# SCH_NFC_Business_Card_2024-01-20.net
KiCad netlist of a schematic drawn in EasyEDA
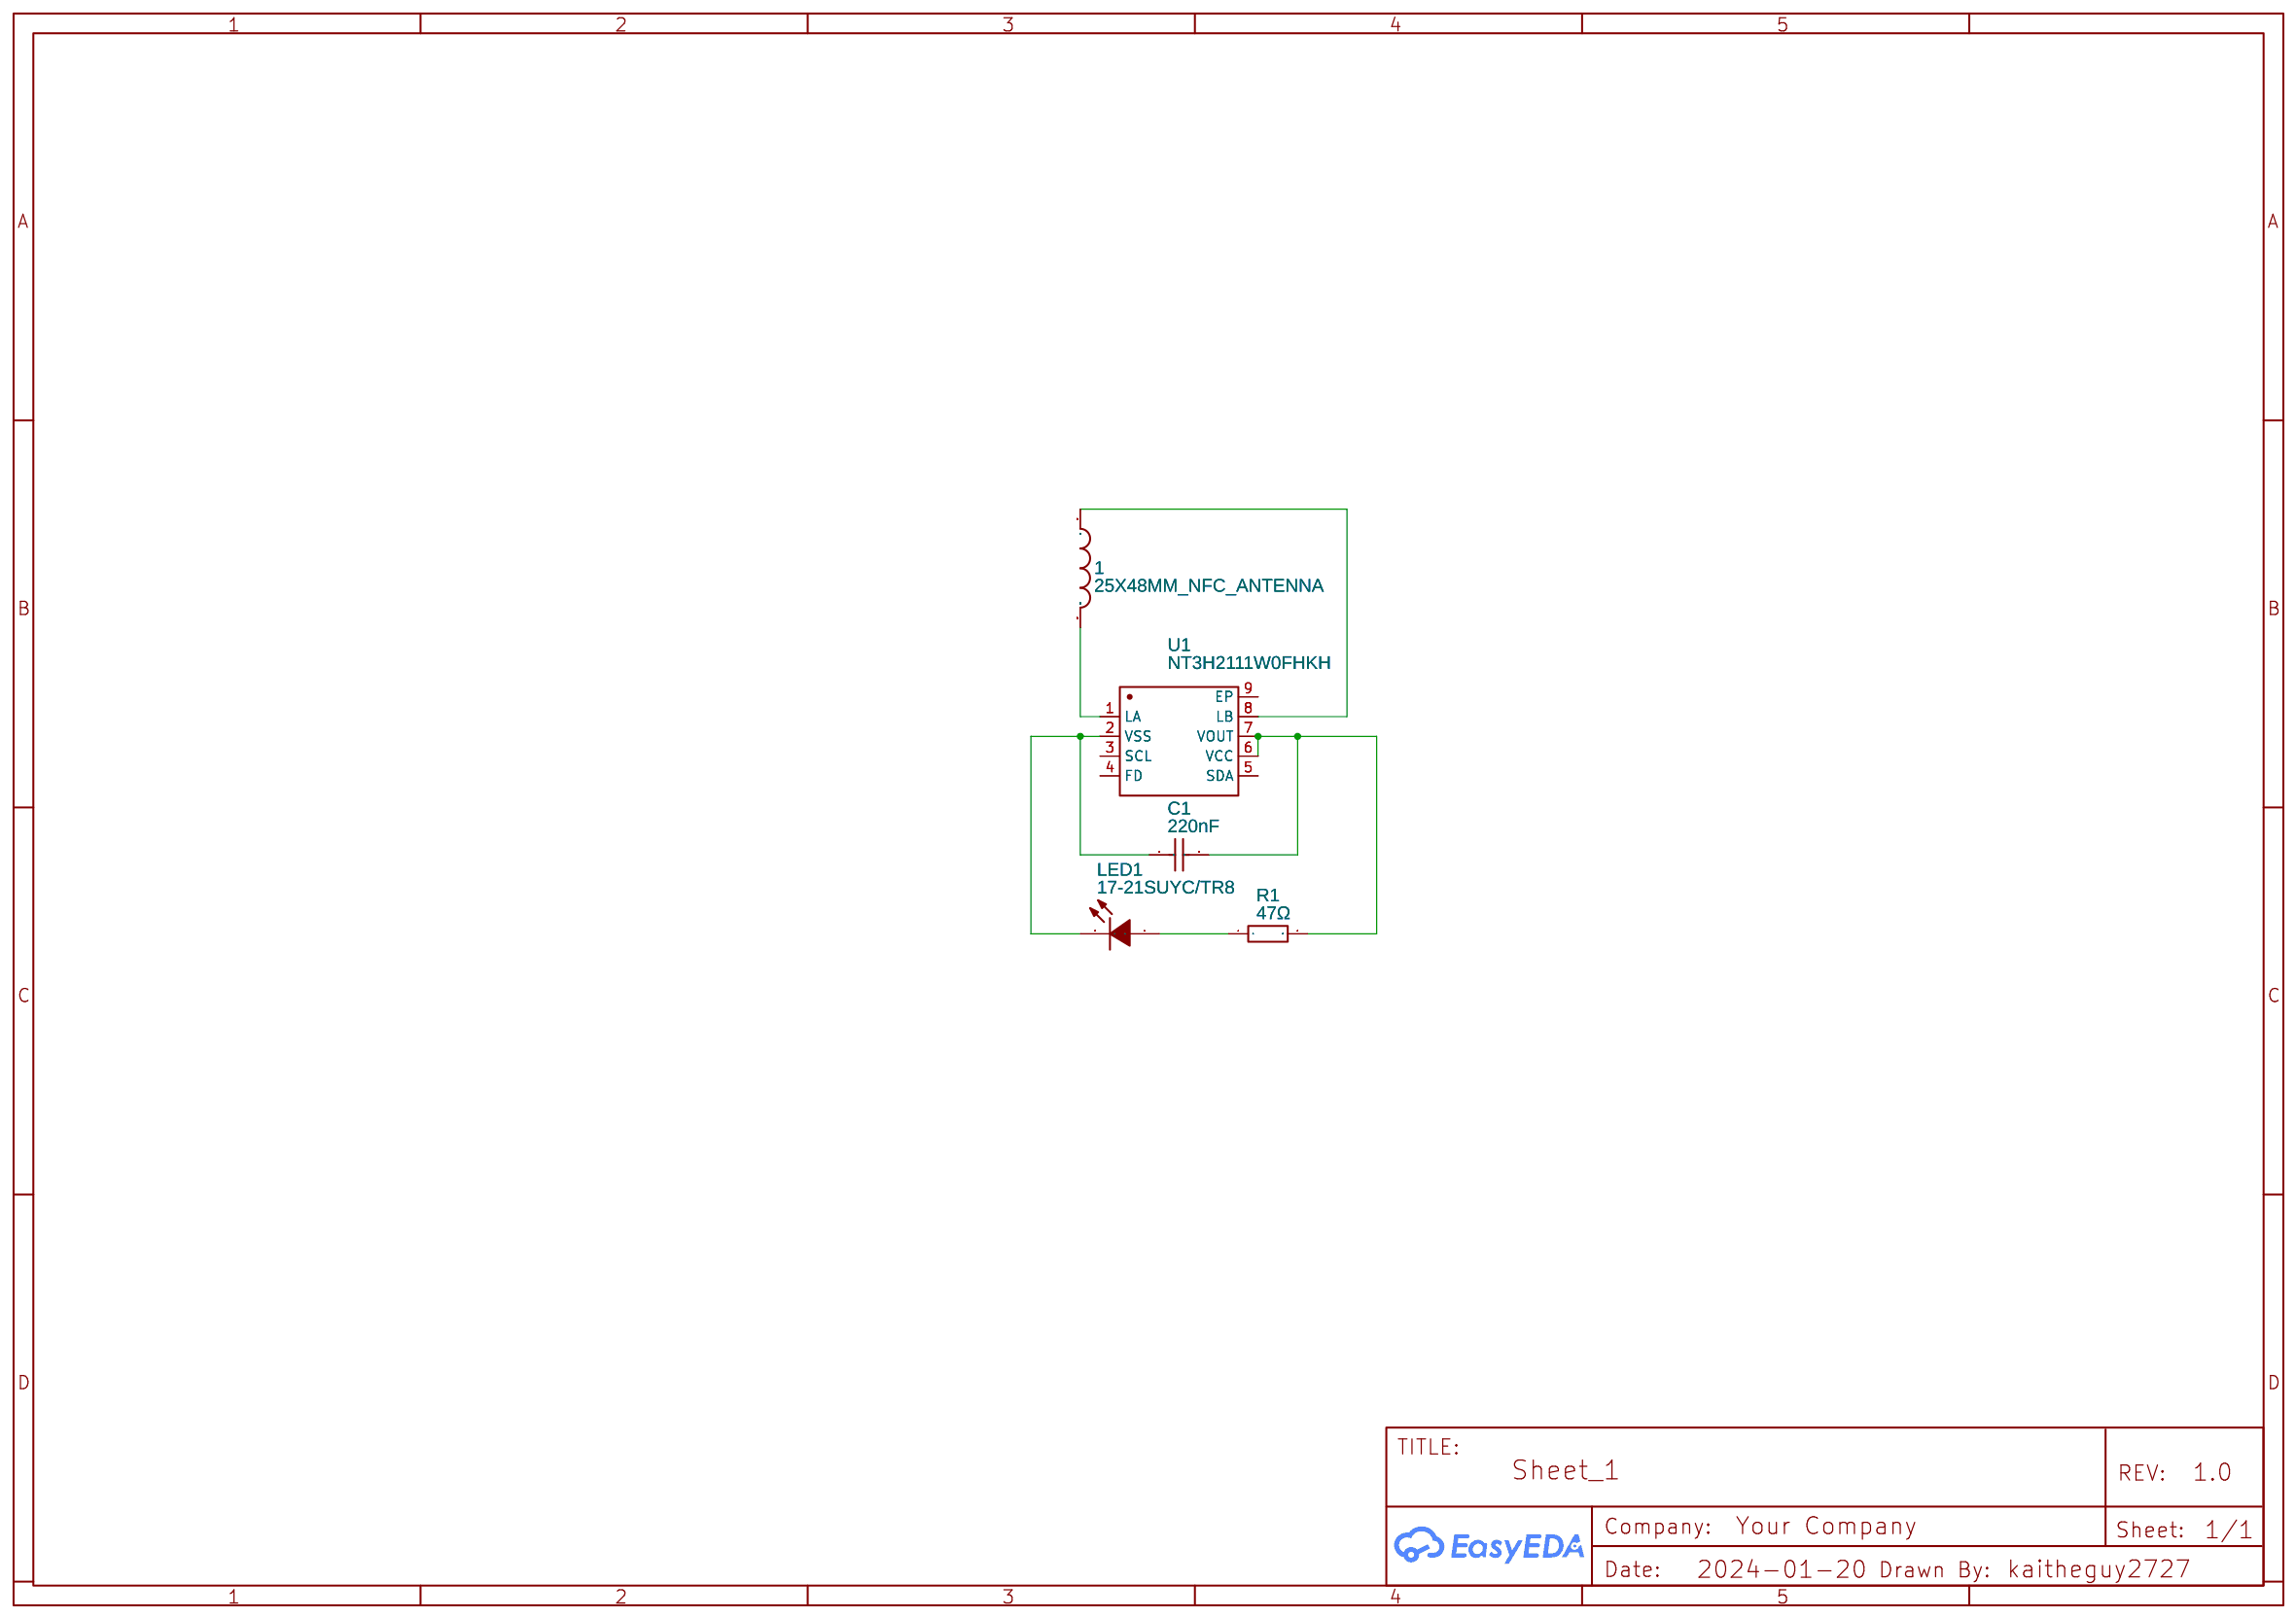
[diagram p0: schematic sheet]

(export (version "E")
  (design (tool "Eeschema 10.0.6"))
  (components
    (comp (ref "1") (value "25X48MM_NFC_ANTENNA") (libsource (lib "") (part "25X48MM_NFC_ANTENNA")))
    (comp (ref "C1")
      (value "220nF")
      (fields
        (field (name "Manufacturer Part") "CL10B224KA8NNNC")
        (field (name "Manufacturer") "SAMSUNG(三星)")
      )
      (libsource (lib "") (part "CL10B224KA8NNNC"))
    )
    (comp (ref "LED1")
      (value "17-21SUYC/TR8")
      (fields (field (name "Manufacturer Part") "KT-0805黄灯") (field (name "Manufacturer") "KENTO"))
      (libsource (lib "") (part "17-21SUYC/TR8"))
    )
    (comp (ref "R1")
      (value "47Ω")
      (fields
        (field (name "Manufacturer Part") "0603WAF470JT5E")
        (field (name "Manufacturer") "UNI-ROYAL(厚声)")
      )
      (libsource (lib "") (part "0603WAF470JT5E"))
    )
    (comp (ref "U1")
      (value "NT3H2111W0FHKH")
      (fields (field (name "Manufacturer") "NXP(恩智浦)"))
      (libsource (lib "") (part "NT3H2111W0FHKH"))
    )
  )
  (nets
    (net (code "1") (name "Net-(LED1-+)") (class "Default")
      (node (ref "LED1") (pin "1") (pinfunction "+_1") (pintype "unspecified"))
      (node (ref "R1") (pin "1") (pinfunction "1_1") (pintype "input"))
    )
    (net (code "2") (name "Net-(LED1--)") (class "Default")
      (node (ref "C1") (pin "1") (pinfunction "1_1") (pintype "input"))
      (node (ref "LED1") (pin "2") (pinfunction "-_2") (pintype "unspecified"))
      (node (ref "U1") (pin "2") (pinfunction "VSS_2") (pintype "unspecified"))
    )
    (net (code "3") (name "Net-(U1-LA)") (class "Default")
      (node (ref "1") (pin "P$2") (pinfunction "P$2_P$2") (pintype "bidirectional"))
      (node (ref "U1") (pin "1") (pinfunction "LA_1") (pintype "unspecified"))
    )
    (net (code "4") (name "Net-(U1-LB)") (class "Default")
      (node (ref "1") (pin "P$1") (pinfunction "P$1_P$1") (pintype "bidirectional"))
      (node (ref "U1") (pin "8") (pinfunction "LB_8") (pintype "unspecified"))
    )
    (net (code "5") (name "Net-(U1-VCC)") (class "Default")
      (node (ref "C1") (pin "2") (pinfunction "2_2") (pintype "input"))
      (node (ref "R1") (pin "2") (pinfunction "2_2") (pintype "input"))
      (node (ref "U1") (pin "6") (pinfunction "VCC_6") (pintype "unspecified"))
      (node (ref "U1") (pin "7") (pinfunction "VOUT_7") (pintype "unspecified"))
    )
    (net (code "6") (name "unconnected-(U1-EP-Pad9)") (class "Default")
      (node (ref "U1") (pin "9") (pinfunction "EP_9") (pintype "unspecified"))
    )
    (net (code "7") (name "unconnected-(U1-FD-Pad4)") (class "Default")
      (node (ref "U1") (pin "4") (pinfunction "FD_4") (pintype "unspecified"))
    )
    (net (code "8") (name "unconnected-(U1-SCL-Pad3)") (class "Default")
      (node (ref "U1") (pin "3") (pinfunction "SCL_3") (pintype "unspecified"))
    )
    (net (code "9") (name "unconnected-(U1-SDA-Pad5)") (class "Default")
      (node (ref "U1") (pin "5") (pinfunction "SDA_5") (pintype "unspecified"))
    )
  )
)
